# heater_control.net
KiCad netlist of a schematic drawn in Altium Designer
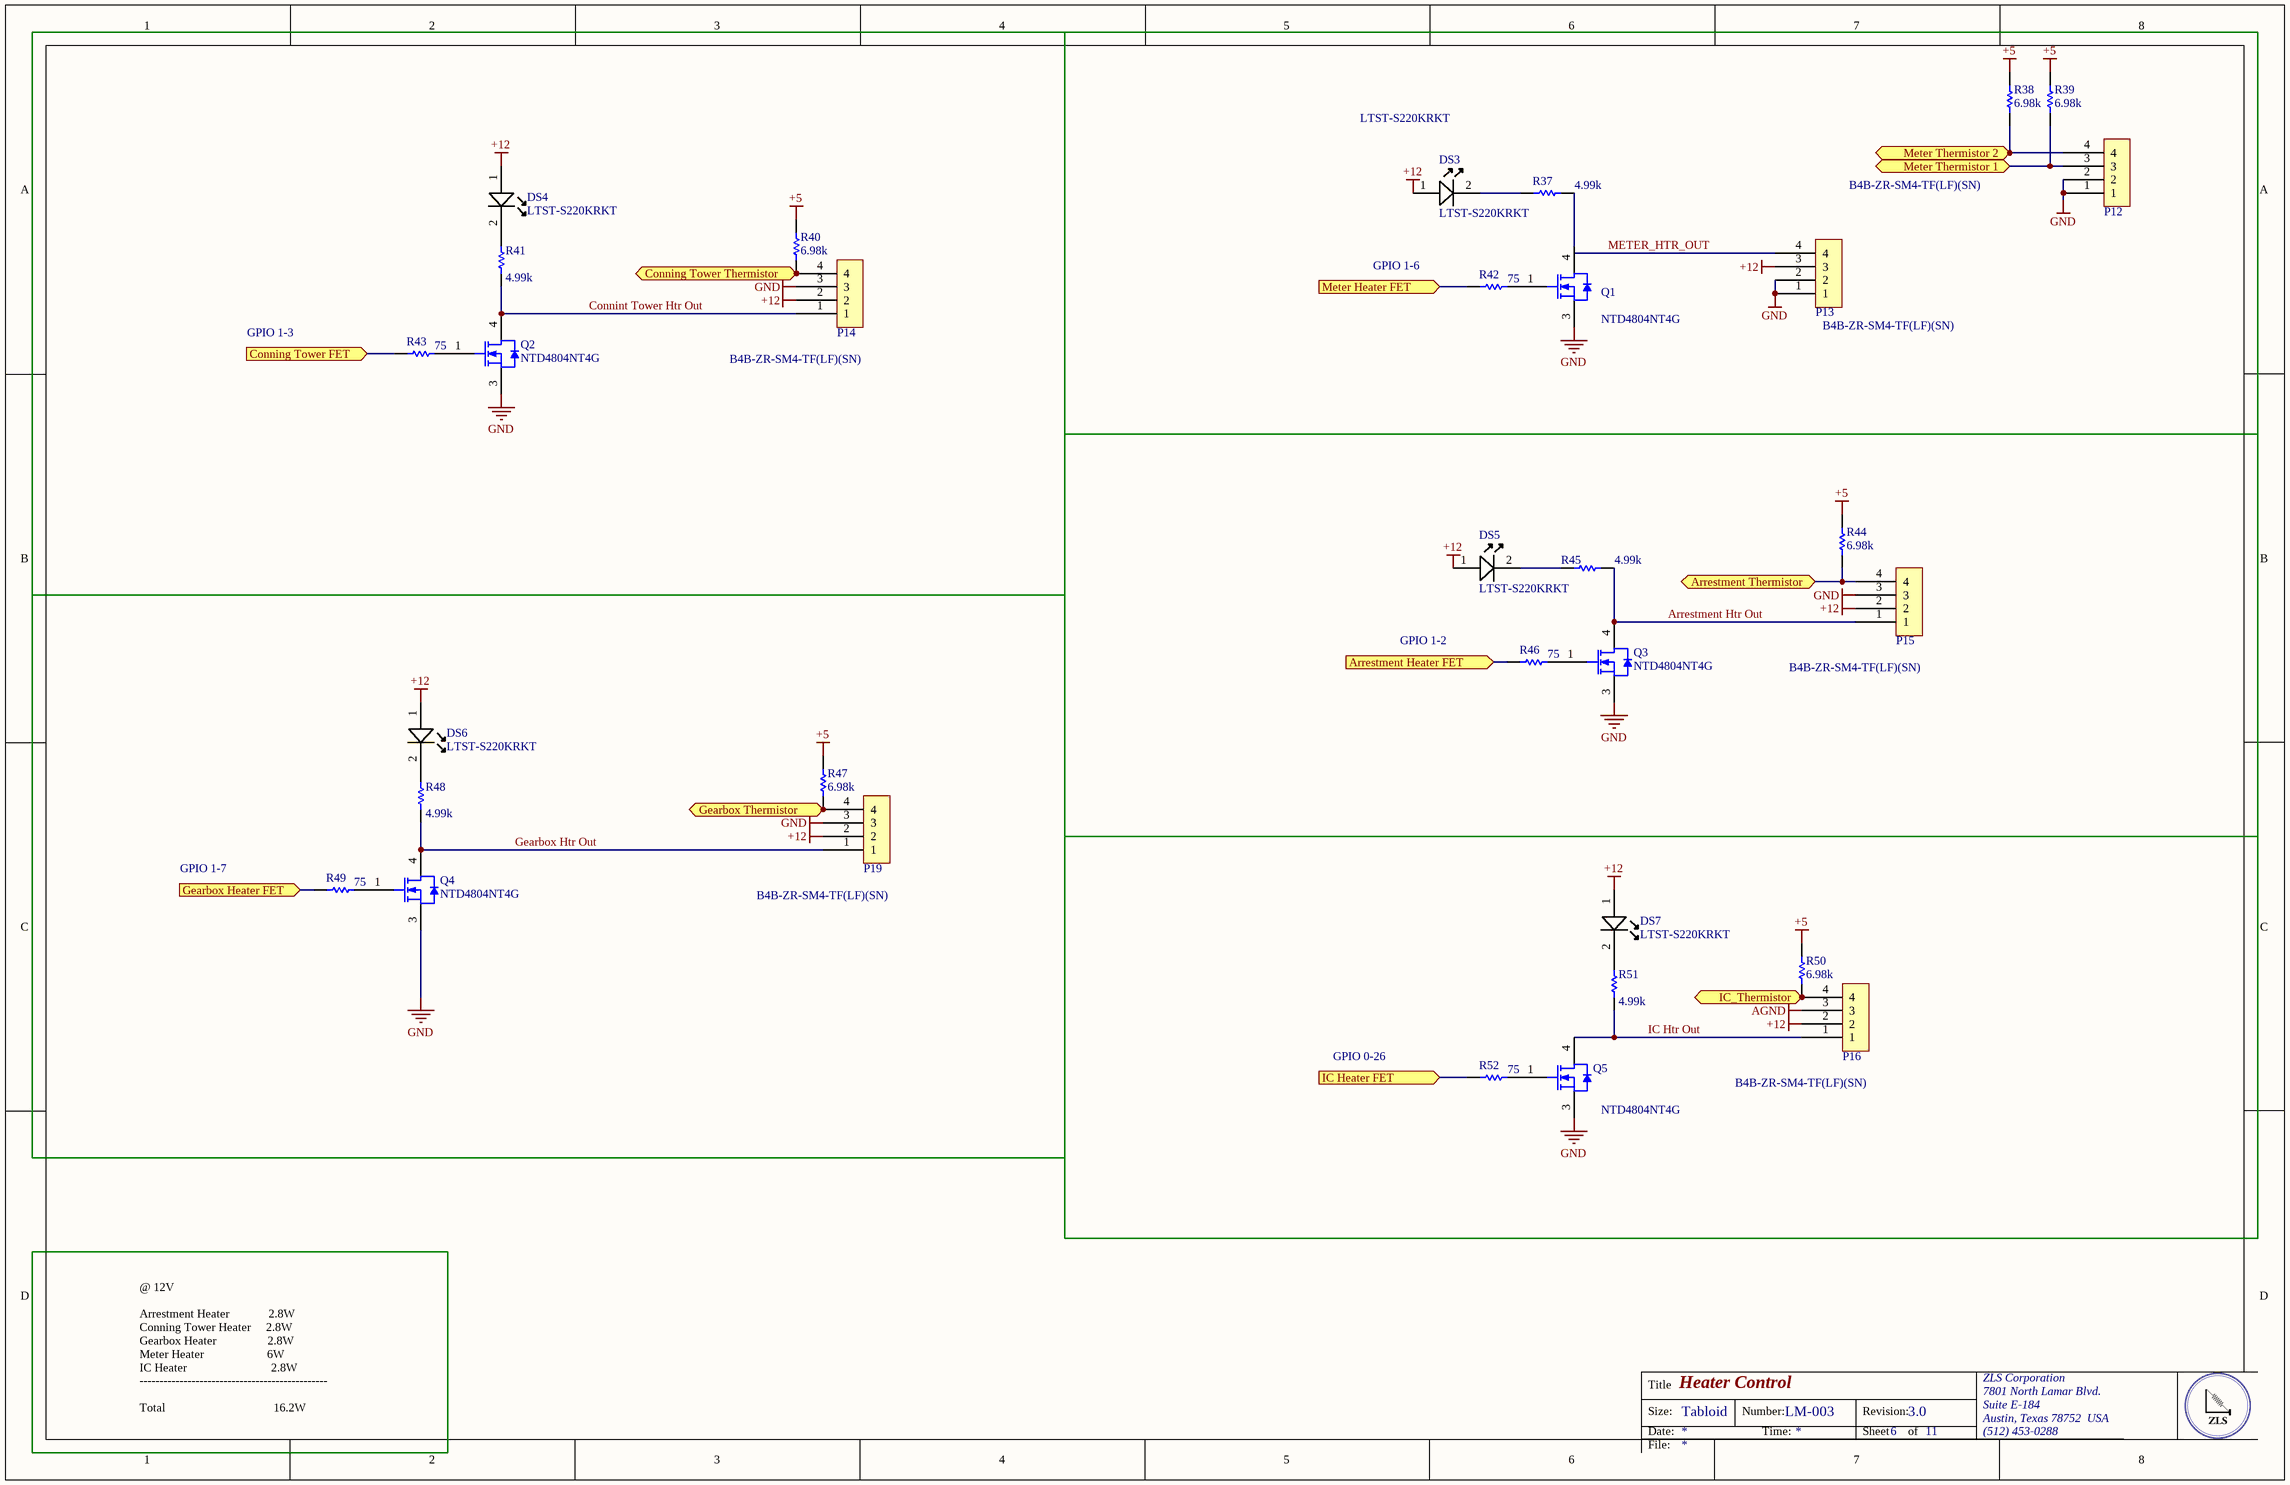
[diagram p0: heater_control.SchDoc]

(export (version "E")
  (design (tool "Eeschema 10.0.6"))
  (components
    (comp (ref "DS3")
      (value "Visible Name Value Type    False Description Lite-On LTST-S220KRKT Red LED, 631 nm 2012 (0805) Side View, Rectangle Lens SMD package STRING")
      (footprint "0805C_L")
      (fields
        (field (name "MANUFACTURER") "Vishay / Lite-On")
        (field (name "MANUFACTURER PART NUMBER") "LTST-S220KRKT")
      )
      (libsource (lib "*") (part "LED A/K"))
    )
    (comp (ref "DS4")
      (value "Visible Name Value Type    False Description Lite-On LTST-S220KRKT Red LED, 631 nm 2012 (0805) Side View, Rectangle Lens SMD package STRING")
      (footprint "0805C_L")
      (fields
        (field (name "MANUFACTURER") "Vishay / Lite-On")
        (field (name "MANUFACTURER PART NUMBER") "LTST-S220KRKT")
      )
      (libsource (lib "*") (part "LED A/K"))
    )
    (comp (ref "DS5")
      (value "Visible Name Value Type    False Description Lite-On LTST-S220KRKT Red LED, 631 nm 2012 (0805) Side View, Rectangle Lens SMD package STRING")
      (footprint "0805C_L")
      (fields
        (field (name "MANUFACTURER") "Vishay / Lite-On")
        (field (name "MANUFACTURER PART NUMBER") "LTST-S220KRKT")
      )
      (libsource (lib "*") (part "LED A/K"))
    )
    (comp (ref "DS6")
      (value "Visible Name Value Type    False Description Lite-On LTST-S220KRKT Red LED, 631 nm 2012 (0805) Side View, Rectangle Lens SMD package STRING")
      (footprint "0805C_L")
      (fields
        (field (name "MANUFACTURER") "Vishay / Lite-On")
        (field (name "MANUFACTURER PART NUMBER") "LTST-S220KRKT")
      )
      (libsource (lib "*") (part "LED A/K"))
    )
    (comp (ref "DS7")
      (value "Visible Name Value Type    False Description Lite-On LTST-S220KRKT Red LED, 631 nm 2012 (0805) Side View, Rectangle Lens SMD package STRING")
      (footprint "0805C_L")
      (fields
        (field (name "MANUFACTURER") "Vishay / Lite-On")
        (field (name "MANUFACTURER PART NUMBER") "LTST-S220KRKT")
      )
      (libsource (lib "*") (part "LED A/K"))
    )
    (comp (ref "P12")
      (value "CONN HEADER ZH TOP 4POS 1.5MM")
      (footprint "B4B-ZR-SM4-TF")
      (fields
        (field (name "MANUFACTURER") "JST Sales America Inc.")
        (field (name "MANUFACTURER PART NUMBER") "B4B-ZR-SM4-TF(LF)(SN)")
      )
      (libsource (lib "ZLS_Schematic_lib") (part "B4B-ZR-SM4-TF"))
    )
    (comp (ref "P13")
      (value "CONN HEADER ZH TOP 4POS 1.5MM")
      (footprint "B4B-ZR-SM4-TF")
      (fields
        (field (name "MANUFACTURER") "JST Sales America Inc.")
        (field (name "MANUFACTURER PART NUMBER") "B4B-ZR-SM4-TF(LF)(SN)")
      )
      (libsource (lib "ZLS_Schematic_lib") (part "B4B-ZR-SM4-TF"))
    )
    (comp (ref "P14")
      (value "CONN HEADER ZH TOP 4POS 1.5MM")
      (footprint "B4B-ZR-SM4-TF")
      (fields
        (field (name "MANUFACTURER") "JST Sales America Inc.")
        (field (name "MANUFACTURER PART NUMBER") "B4B-ZR-SM4-TF(LF)(SN)")
      )
      (libsource (lib "ZLS_Schematic_lib") (part "B4B-ZR-SM4-TF"))
    )
    (comp (ref "P15")
      (value "CONN HEADER ZH TOP 4POS 1.5MM")
      (footprint "B4B-ZR-SM4-TF")
      (fields
        (field (name "MANUFACTURER") "JST Sales America Inc.")
        (field (name "MANUFACTURER PART NUMBER") "B4B-ZR-SM4-TF(LF)(SN)")
      )
      (libsource (lib "ZLS_Schematic_lib") (part "B4B-ZR-SM4-TF"))
    )
    (comp (ref "P16")
      (value "CONN HEADER ZH TOP 4POS 1.5MM")
      (footprint "B4B-ZR-SM4-TF")
      (fields
        (field (name "MANUFACTURER") "JST Sales America Inc.")
        (field (name "MANUFACTURER PART NUMBER") "B4B-ZR-SM4-TF(LF)(SN)")
      )
      (libsource (lib "ZLS_Schematic_lib") (part "B4B-ZR-SM4-TF"))
    )
    (comp (ref "P19")
      (value "CONN HEADER ZH TOP 4POS 1.5MM")
      (footprint "B4B-ZR-SM4-TF")
      (fields
        (field (name "MANUFACTURER") "JST Sales America Inc.")
        (field (name "MANUFACTURER PART NUMBER") "B4B-ZR-SM4-TF(LF)(SN)")
      )
      (libsource (lib "ZLS_Schematic_lib") (part "B4B-ZR-SM4-TF"))
    )
    (comp (ref "Q1")
      (value "NTD4804NT4G")
      (footprint "ONSC-DPAK-3-369AA-01_V")
      (description "Power MOSFET, 30 V, 117 A, Single N-Channel, 3-Pin DPAK, Pb-Free, Tape and Reel")
      (fields (field (name "MANUFACTURER") "On Semiconductor"))
      (libsource (lib "Altium Content Vault") (part "CMP-1058-00341-1"))
    )
    (comp (ref "Q2")
      (value "NTD4804NT4G")
      (footprint "ONSC-DPAK-3-369AA-01_V")
      (description "Power MOSFET, 30 V, 117 A, Single N-Channel, 3-Pin DPAK, Pb-Free, Tape and Reel")
      (fields (field (name "MANUFACTURER") "On Semiconductor"))
      (libsource (lib "Altium Content Vault") (part "CMP-1058-00341-1"))
    )
    (comp (ref "Q3")
      (value "NTD4804NT4G")
      (footprint "ONSC-DPAK-3-369AA-01_V")
      (description "Power MOSFET, 30 V, 117 A, Single N-Channel, 3-Pin DPAK, Pb-Free, Tape and Reel")
      (fields (field (name "MANUFACTURER") "On Semiconductor"))
      (libsource (lib "Altium Content Vault") (part "CMP-1058-00341-1"))
    )
    (comp (ref "Q4")
      (value "NTD4804NT4G")
      (footprint "ONSC-DPAK-3-369AA-01_V")
      (description "Power MOSFET, 30 V, 117 A, Single N-Channel, 3-Pin DPAK, Pb-Free, Tape and Reel")
      (fields (field (name "MANUFACTURER") "On Semiconductor"))
      (libsource (lib "Altium Content Vault") (part "CMP-1058-00341-1"))
    )
    (comp (ref "Q5")
      (value "NTD4804NT4G")
      (footprint "ONSC-DPAK-3-369AA-01_V")
      (description "Power MOSFET, 30 V, 117 A, Single N-Channel, 3-Pin DPAK, Pb-Free, Tape and Reel")
      (fields (field (name "MANUFACTURER") "On Semiconductor"))
      (libsource (lib "Altium Content Vault") (part "CMP-1058-00341-1"))
    )
    (comp (ref "R37")
      (value "~")
      (footprint "RESC0805(2012)_L")
      (fields
        (field (name "MANUFACTURER") "Vishay Dale")
        (field (name "MANUFACTURER PART NUMBER") "CRCW08054K99FKEA")
        (field (name "RESISTANCE (OHMS)") "4.99k")
        (field (name "TOLERANCE") "±1%")
      )
      (libsource (lib "Altium Content Vault") (part "CMP-1013-00393-1"))
    )
    (comp (ref "R38")
      (value "6K98 1% 0805(2012)")
      (footprint "RESC0805(2012)_N")
      (description "6K98 0.125W 1% 0805 (2012 Metric)  SMD")
      (fields
        (field (name "MANUFACTURER") "Vishay Dale")
        (field (name "MANUFACTURER PART NUMBER") "CRCW08056K98FKEA")
        (field (name "RESISTANCE (OHMS)") "6.98k")
      )
      (libsource (lib "Altium Content Vault") (part "CMP-1013-00606-1"))
    )
    (comp (ref "R39")
      (value "6K98 1% 0805(2012)")
      (footprint "RESC0805(2012)_N")
      (description "6K98 0.125W 1% 0805 (2012 Metric)  SMD")
      (fields
        (field (name "MANUFACTURER") "Vishay Dale")
        (field (name "MANUFACTURER PART NUMBER") "CRCW08056K98FKEA")
        (field (name "RESISTANCE (OHMS)") "6.98k")
      )
      (libsource (lib "Altium Content Vault") (part "CMP-1013-00606-1"))
    )
    (comp (ref "R40")
      (value "6K98 1% 0805(2012)")
      (footprint "RESC0805(2012)_N")
      (description "6K98 0.125W 1% 0805 (2012 Metric)  SMD")
      (fields
        (field (name "MANUFACTURER") "Vishay Dale")
        (field (name "MANUFACTURER PART NUMBER") "CRCW08056K98FKEA")
        (field (name "RESISTANCE (OHMS)") "6.98k")
      )
      (libsource (lib "Altium Content Vault") (part "CMP-1013-00606-1"))
    )
    (comp (ref "R41")
      (value "~")
      (footprint "RESC0805(2012)_L")
      (fields
        (field (name "MANUFACTURER") "Vishay Dale")
        (field (name "MANUFACTURER PART NUMBER") "CRCW08054K99FKEA")
        (field (name "RESISTANCE (OHMS)") "4.99k")
        (field (name "TOLERANCE") "±1%")
      )
      (libsource (lib "Altium Content Vault") (part "CMP-1013-00393-1"))
    )
    (comp (ref "R42")
      (value "~")
      (footprint "RESC0805(2012)_L")
      (fields
        (field (name "MANUFACTURER") "Vishay Dale")
        (field (name "MANUFACTURER PART NUMBER") "CRCW080575R0FKEA")
        (field (name "RESISTANCE (OHMS)") "75")
        (field (name "TOLERANCE") "±1%")
      )
      (libsource (lib "Altium Content Vault") (part "CMP-1013-00393-1"))
    )
    (comp (ref "R43")
      (value "~")
      (footprint "RESC0805(2012)_L")
      (fields
        (field (name "MANUFACTURER") "Vishay Dale")
        (field (name "MANUFACTURER PART NUMBER") "CRCW080575R0FKEA")
        (field (name "RESISTANCE (OHMS)") "75")
        (field (name "TOLERANCE") "±1%")
      )
      (libsource (lib "Altium Content Vault") (part "CMP-1013-00393-1"))
    )
    (comp (ref "R44")
      (value "6K98 1% 0805(2012)")
      (footprint "RESC0805(2012)_N")
      (description "6K98 0.125W 1% 0805 (2012 Metric)  SMD")
      (fields
        (field (name "MANUFACTURER") "Vishay Dale")
        (field (name "MANUFACTURER PART NUMBER") "CRCW08056K98FKEA")
        (field (name "RESISTANCE (OHMS)") "6.98k")
      )
      (libsource (lib "Altium Content Vault") (part "CMP-1013-00606-1"))
    )
    (comp (ref "R45")
      (value "~")
      (footprint "RESC0805(2012)_L")
      (fields
        (field (name "MANUFACTURER") "Vishay Dale")
        (field (name "MANUFACTURER PART NUMBER") "CRCW08054K99FKEA")
        (field (name "RESISTANCE (OHMS)") "4.99k")
        (field (name "TOLERANCE") "±1%")
      )
      (libsource (lib "Altium Content Vault") (part "CMP-1013-00393-1"))
    )
    (comp (ref "R46")
      (value "~")
      (footprint "RESC0805(2012)_L")
      (fields
        (field (name "MANUFACTURER") "Vishay Dale")
        (field (name "MANUFACTURER PART NUMBER") "CRCW080575R0FKEA")
        (field (name "RESISTANCE (OHMS)") "75")
        (field (name "TOLERANCE") "±1%")
      )
      (libsource (lib "Altium Content Vault") (part "CMP-1013-00393-1"))
    )
    (comp (ref "R47")
      (value "6K98 1% 0805(2012)")
      (footprint "RESC0805(2012)_N")
      (description "6K98 0.125W 1% 0805 (2012 Metric)  SMD")
      (fields
        (field (name "MANUFACTURER") "Vishay Dale")
        (field (name "MANUFACTURER PART NUMBER") "CRCW08056K98FKEA")
        (field (name "RESISTANCE (OHMS)") "6.98k")
      )
      (libsource (lib "Altium Content Vault") (part "CMP-1013-00606-1"))
    )
    (comp (ref "R48")
      (value "~")
      (footprint "RESC0805(2012)_L")
      (fields
        (field (name "MANUFACTURER") "Vishay Dale")
        (field (name "MANUFACTURER PART NUMBER") "CRCW08054K99FKEA")
        (field (name "RESISTANCE (OHMS)") "4.99k")
        (field (name "TOLERANCE") "±1%")
      )
      (libsource (lib "Altium Content Vault") (part "CMP-1013-00393-1"))
    )
    (comp (ref "R49")
      (value "~")
      (footprint "RESC0805(2012)_L")
      (fields
        (field (name "MANUFACTURER") "Vishay Dale")
        (field (name "MANUFACTURER PART NUMBER") "CRCW080575R0FKEA")
        (field (name "RESISTANCE (OHMS)") "75")
        (field (name "TOLERANCE") "±1%")
      )
      (libsource (lib "Altium Content Vault") (part "CMP-1013-00393-1"))
    )
    (comp (ref "R50")
      (value "6K98 1% 0805(2012)")
      (footprint "RESC0805(2012)_N")
      (description "6K98 0.125W 1% 0805 (2012 Metric)  SMD")
      (fields
        (field (name "MANUFACTURER") "Vishay Dale")
        (field (name "MANUFACTURER PART NUMBER") "CRCW08056K98FKEA")
        (field (name "RESISTANCE (OHMS)") "6.98k")
      )
      (libsource (lib "Altium Content Vault") (part "CMP-1013-00606-1"))
    )
    (comp (ref "R51")
      (value "~")
      (footprint "RESC0805(2012)_L")
      (fields
        (field (name "MANUFACTURER") "Vishay Dale")
        (field (name "MANUFACTURER PART NUMBER") "CRCW08054K99FKEA")
        (field (name "RESISTANCE (OHMS)") "4.99k")
        (field (name "TOLERANCE") "±1%")
      )
      (libsource (lib "Altium Content Vault") (part "CMP-1013-00393-1"))
    )
    (comp (ref "R52")
      (value "~")
      (footprint "RESC0805(2012)_L")
      (fields
        (field (name "MANUFACTURER") "Vishay Dale")
        (field (name "MANUFACTURER PART NUMBER") "CRCW080575R0FKEA")
        (field (name "RESISTANCE (OHMS)") "75")
        (field (name "TOLERANCE") "±1%")
      )
      (libsource (lib "Altium Content Vault") (part "CMP-1013-00393-1"))
    )
  )
  (nets
    (net (code "1") (name "+5") (class "Default")
      (node (ref "R38") (pin "1") (pinfunction "1_1") (pintype "passive"))
      (node (ref "R39") (pin "2") (pinfunction "2_2") (pintype "passive"))
      (node (ref "R40") (pin "2") (pinfunction "2_2") (pintype "passive"))
      (node (ref "R44") (pin "1") (pinfunction "1_1") (pintype "passive"))
      (node (ref "R47") (pin "2") (pinfunction "2_2") (pintype "passive"))
      (node (ref "R50") (pin "1") (pinfunction "1_1") (pintype "passive"))
    )
    (net (code "2") (name "+12") (class "Default")
      (node (ref "DS3") (pin "1") (pinfunction "A_1") (pintype "passive"))
      (node (ref "DS4") (pin "1") (pinfunction "A_1") (pintype "passive"))
      (node (ref "DS5") (pin "1") (pinfunction "A_1") (pintype "passive"))
      (node (ref "DS6") (pin "1") (pinfunction "A_1") (pintype "passive"))
      (node (ref "DS7") (pin "1") (pinfunction "A_1") (pintype "passive"))
      (node (ref "P13") (pin "3") (pinfunction "3_3") (pintype "passive"))
      (node (ref "P14") (pin "2") (pinfunction "2_2") (pintype "passive"))
      (node (ref "P15") (pin "2") (pinfunction "2_2") (pintype "passive"))
      (node (ref "P16") (pin "2") (pinfunction "2_2") (pintype "passive"))
      (node (ref "P19") (pin "2") (pinfunction "2_2") (pintype "passive"))
    )
    (net (code "3") (name "/Arrestment Heater FET") (class "Default")
      (node (ref "R46") (pin "1") (pinfunction "1_1") (pintype "passive"))
    )
    (net (code "4") (name "/Arrestment Htr Out") (class "Default")
      (node (ref "P15") (pin "1") (pinfunction "1_1") (pintype "passive"))
      (node (ref "Q3") (pin "4") (pinfunction "D_4") (pintype "passive"))
      (node (ref "R45") (pin "2") (pinfunction "2_2") (pintype "passive"))
    )
    (net (code "5") (name "/Arrestment Thermistor") (class "Default")
      (node (ref "P15") (pin "4") (pinfunction "4_4") (pintype "passive"))
      (node (ref "R44") (pin "2") (pinfunction "2_2") (pintype "passive"))
    )
    (net (code "6") (name "/Conning Tower FET") (class "Default")
      (node (ref "R43") (pin "1") (pinfunction "1_1") (pintype "passive"))
    )
    (net (code "7") (name "/Conning Tower Thermistor") (class "Default")
      (node (ref "P14") (pin "4") (pinfunction "4_4") (pintype "passive"))
      (node (ref "R40") (pin "1") (pinfunction "1_1") (pintype "passive"))
    )
    (net (code "8") (name "/Connint Tower Htr Out") (class "Default")
      (node (ref "P14") (pin "1") (pinfunction "1_1") (pintype "passive"))
      (node (ref "Q2") (pin "4") (pinfunction "D_4") (pintype "passive"))
      (node (ref "R41") (pin "1") (pinfunction "1_1") (pintype "passive"))
    )
    (net (code "9") (name "/Gearbox Heater FET") (class "Default")
      (node (ref "R49") (pin "1") (pinfunction "1_1") (pintype "passive"))
    )
    (net (code "10") (name "/Gearbox Htr Out") (class "Default")
      (node (ref "P19") (pin "1") (pinfunction "1_1") (pintype "passive"))
      (node (ref "Q4") (pin "4") (pinfunction "D_4") (pintype "passive"))
      (node (ref "R48") (pin "1") (pinfunction "1_1") (pintype "passive"))
    )
    (net (code "11") (name "/Gearbox Thermistor") (class "Default")
      (node (ref "P19") (pin "4") (pinfunction "4_4") (pintype "passive"))
      (node (ref "R47") (pin "1") (pinfunction "1_1") (pintype "passive"))
    )
    (net (code "12") (name "/IC Heater FET") (class "Default")
      (node (ref "R52") (pin "1") (pinfunction "1_1") (pintype "passive"))
    )
    (net (code "13") (name "/IC Htr Out") (class "Default")
      (node (ref "P16") (pin "1") (pinfunction "1_1") (pintype "passive"))
      (node (ref "Q5") (pin "4") (pinfunction "D_4") (pintype "passive"))
      (node (ref "R51") (pin "2") (pinfunction "2_2") (pintype "passive"))
    )
    (net (code "14") (name "/IC_Thermistor") (class "Default")
      (node (ref "P16") (pin "4") (pinfunction "4_4") (pintype "passive"))
      (node (ref "R50") (pin "2") (pinfunction "2_2") (pintype "passive"))
    )
    (net (code "15") (name "/METER_HTR_OUT") (class "Default")
      (node (ref "P13") (pin "4") (pinfunction "4_4") (pintype "passive"))
    )
    (net (code "16") (name "/Meter Heater FET") (class "Default")
      (node (ref "R42") (pin "1") (pinfunction "1_1") (pintype "passive"))
    )
    (net (code "17") (name "/Meter Thermistor 1") (class "Default")
      (node (ref "P12") (pin "3") (pinfunction "3_3") (pintype "passive"))
      (node (ref "R39") (pin "1") (pinfunction "1_1") (pintype "passive"))
    )
    (net (code "18") (name "/Meter Thermistor 2") (class "Default")
      (node (ref "P12") (pin "4") (pinfunction "4_4") (pintype "passive"))
      (node (ref "R38") (pin "2") (pinfunction "2_2") (pintype "passive"))
    )
    (net (code "19") (name "AGND") (class "Default")
      (node (ref "P16") (pin "3") (pinfunction "3_3") (pintype "passive"))
    )
    (net (code "20") (name "GND") (class "Default")
      (node (ref "P12") (pin "1") (pinfunction "1_1") (pintype "passive"))
      (node (ref "P12") (pin "2") (pinfunction "2_2") (pintype "passive"))
      (node (ref "P13") (pin "1") (pinfunction "1_1") (pintype "passive"))
      (node (ref "P13") (pin "2") (pinfunction "2_2") (pintype "passive"))
      (node (ref "P14") (pin "3") (pinfunction "3_3") (pintype "passive"))
      (node (ref "P15") (pin "3") (pinfunction "3_3") (pintype "passive"))
      (node (ref "P19") (pin "3") (pinfunction "3_3") (pintype "passive"))
      (node (ref "Q1") (pin "3") (pinfunction "S_3") (pintype "passive"))
      (node (ref "Q2") (pin "3") (pinfunction "S_3") (pintype "passive"))
      (node (ref "Q3") (pin "3") (pinfunction "S_3") (pintype "passive"))
      (node (ref "Q4") (pin "3") (pinfunction "S_3") (pintype "passive"))
      (node (ref "Q5") (pin "3") (pinfunction "S_3") (pintype "passive"))
    )
    (net (code "21") (name "Net-(DS3-K)") (class "Default")
      (node (ref "DS3") (pin "2") (pinfunction "K_2") (pintype "passive"))
      (node (ref "R37") (pin "1") (pinfunction "1_1") (pintype "passive"))
    )
    (net (code "22") (name "Net-(DS4-K)") (class "Default")
      (node (ref "DS4") (pin "2") (pinfunction "K_2") (pintype "passive"))
      (node (ref "R41") (pin "2") (pinfunction "2_2") (pintype "passive"))
    )
    (net (code "23") (name "Net-(DS5-K)") (class "Default")
      (node (ref "DS5") (pin "2") (pinfunction "K_2") (pintype "passive"))
      (node (ref "R45") (pin "1") (pinfunction "1_1") (pintype "passive"))
    )
    (net (code "24") (name "Net-(DS6-K)") (class "Default")
      (node (ref "DS6") (pin "2") (pinfunction "K_2") (pintype "passive"))
      (node (ref "R48") (pin "2") (pinfunction "2_2") (pintype "passive"))
    )
    (net (code "25") (name "Net-(DS7-K)") (class "Default")
      (node (ref "DS7") (pin "2") (pinfunction "K_2") (pintype "passive"))
      (node (ref "R51") (pin "1") (pinfunction "1_1") (pintype "passive"))
    )
    (net (code "26") (name "Net-(Q1-D)") (class "Default")
      (node (ref "Q1") (pin "4") (pinfunction "D_4") (pintype "passive"))
      (node (ref "R37") (pin "2") (pinfunction "2_2") (pintype "passive"))
    )
    (net (code "27") (name "Net-(Q1-G)") (class "Default")
      (node (ref "Q1") (pin "1") (pinfunction "G_1") (pintype "passive"))
      (node (ref "R42") (pin "2") (pinfunction "2_2") (pintype "passive"))
    )
    (net (code "28") (name "Net-(Q2-G)") (class "Default")
      (node (ref "Q2") (pin "1") (pinfunction "G_1") (pintype "passive"))
      (node (ref "R43") (pin "2") (pinfunction "2_2") (pintype "passive"))
    )
    (net (code "29") (name "Net-(Q3-G)") (class "Default")
      (node (ref "Q3") (pin "1") (pinfunction "G_1") (pintype "passive"))
      (node (ref "R46") (pin "2") (pinfunction "2_2") (pintype "passive"))
    )
    (net (code "30") (name "Net-(Q4-G)") (class "Default")
      (node (ref "Q4") (pin "1") (pinfunction "G_1") (pintype "passive"))
      (node (ref "R49") (pin "2") (pinfunction "2_2") (pintype "passive"))
    )
    (net (code "31") (name "Net-(Q5-G)") (class "Default")
      (node (ref "Q5") (pin "1") (pinfunction "G_1") (pintype "passive"))
      (node (ref "R52") (pin "2") (pinfunction "2_2") (pintype "passive"))
    )
    (net (code "32") (name "unconnected-(P12-Pad5)") (class "Default")
      (node (ref "P12") (pin "5") (pinfunction "5_5") (pintype "passive"))
    )
    (net (code "33") (name "unconnected-(P12-Pad6)") (class "Default")
      (node (ref "P12") (pin "6") (pinfunction "6_6") (pintype "passive"))
    )
    (net (code "34") (name "unconnected-(P13-Pad5)") (class "Default")
      (node (ref "P13") (pin "5") (pinfunction "5_5") (pintype "passive"))
    )
    (net (code "35") (name "unconnected-(P13-Pad6)") (class "Default")
      (node (ref "P13") (pin "6") (pinfunction "6_6") (pintype "passive"))
    )
    (net (code "36") (name "unconnected-(P14-Pad5)") (class "Default")
      (node (ref "P14") (pin "5") (pinfunction "5_5") (pintype "passive"))
    )
    (net (code "37") (name "unconnected-(P14-Pad6)") (class "Default")
      (node (ref "P14") (pin "6") (pinfunction "6_6") (pintype "passive"))
    )
    (net (code "38") (name "unconnected-(P15-Pad5)") (class "Default")
      (node (ref "P15") (pin "5") (pinfunction "5_5") (pintype "passive"))
    )
    (net (code "39") (name "unconnected-(P15-Pad6)") (class "Default")
      (node (ref "P15") (pin "6") (pinfunction "6_6") (pintype "passive"))
    )
    (net (code "40") (name "unconnected-(P16-Pad5)") (class "Default")
      (node (ref "P16") (pin "5") (pinfunction "5_5") (pintype "passive"))
    )
    (net (code "41") (name "unconnected-(P16-Pad6)") (class "Default")
      (node (ref "P16") (pin "6") (pinfunction "6_6") (pintype "passive"))
    )
    (net (code "42") (name "unconnected-(P19-Pad5)") (class "Default")
      (node (ref "P19") (pin "5") (pinfunction "5_5") (pintype "passive"))
    )
    (net (code "43") (name "unconnected-(P19-Pad6)") (class "Default")
      (node (ref "P19") (pin "6") (pinfunction "6_6") (pintype "passive"))
    )
  )
)
